# IO4-IR-Detector-Active-Fingers.net
KiCad netlist of a schematic drawn in EAGLE
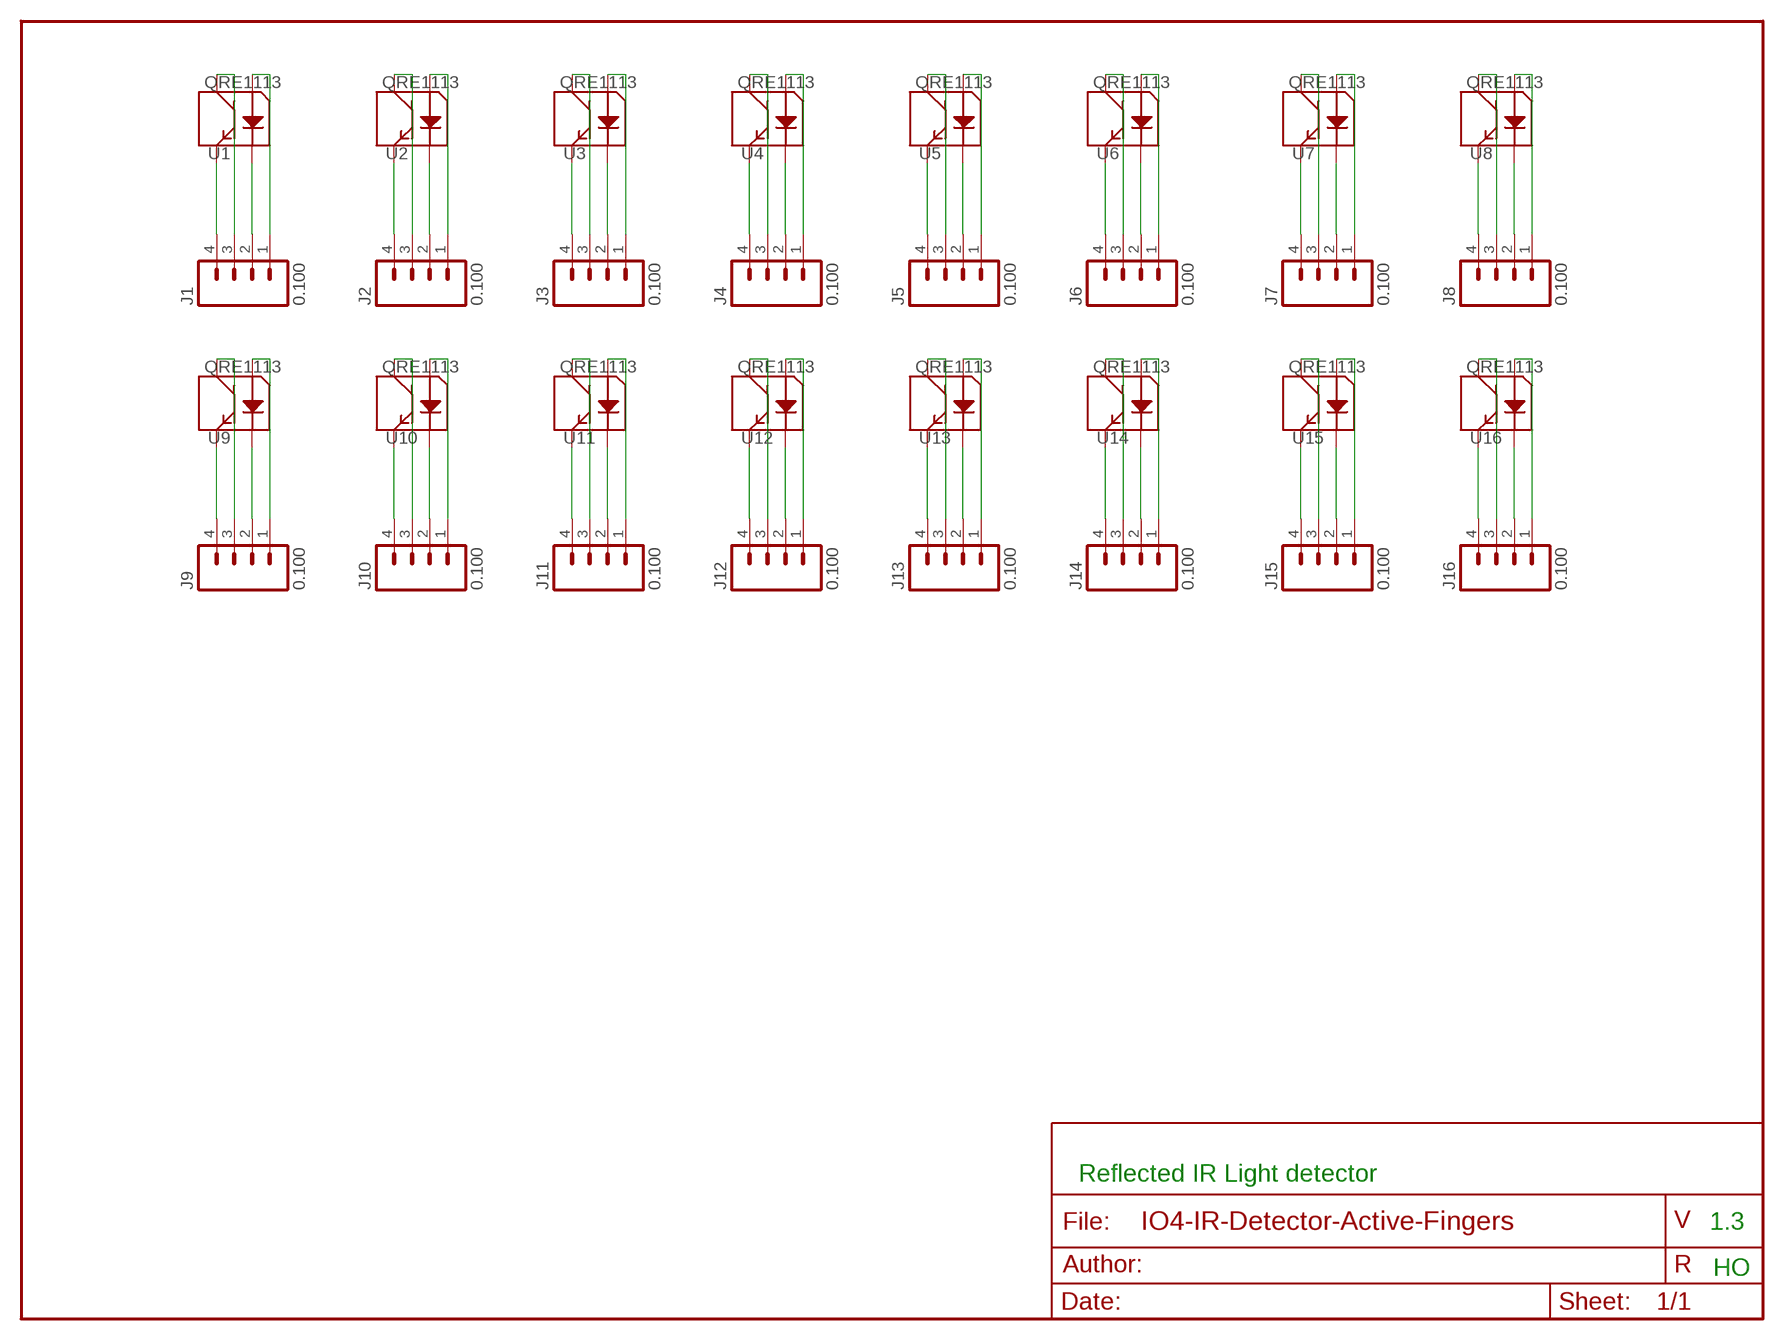
[diagram p0: schematic, sheet 1]

(export (version "E")
  (design (tool "Eeschema 10.0.6"))
  (components
    (comp (ref "J1")
      (value "0.100")
      (footprint "eagle-import:1X04_LOCK")
      (libsource (lib "eagle-import") (part "CONNECTOR-M04LOCK"))
    )
    (comp (ref "J2")
      (value "0.100")
      (footprint "eagle-import:1X04_LOCK")
      (libsource (lib "eagle-import") (part "CONNECTOR-M04LOCK"))
    )
    (comp (ref "J3")
      (value "0.100")
      (footprint "eagle-import:1X04_LOCK")
      (libsource (lib "eagle-import") (part "CONNECTOR-M04LOCK"))
    )
    (comp (ref "J4")
      (value "0.100")
      (footprint "eagle-import:1X04_LOCK")
      (libsource (lib "eagle-import") (part "CONNECTOR-M04LOCK"))
    )
    (comp (ref "J5")
      (value "0.100")
      (footprint "eagle-import:1X04_LOCK")
      (libsource (lib "eagle-import") (part "CONNECTOR-M04LOCK"))
    )
    (comp (ref "J6")
      (value "0.100")
      (footprint "eagle-import:1X04_LOCK")
      (libsource (lib "eagle-import") (part "CONNECTOR-M04LOCK"))
    )
    (comp (ref "J7")
      (value "0.100")
      (footprint "eagle-import:1X04_LOCK")
      (libsource (lib "eagle-import") (part "CONNECTOR-M04LOCK"))
    )
    (comp (ref "J8")
      (value "0.100")
      (footprint "eagle-import:1X04_LOCK")
      (libsource (lib "eagle-import") (part "CONNECTOR-M04LOCK"))
    )
    (comp (ref "J9")
      (value "0.100")
      (footprint "eagle-import:1X04_LOCK")
      (libsource (lib "eagle-import") (part "CONNECTOR-M04LOCK"))
    )
    (comp (ref "J10")
      (value "0.100")
      (footprint "eagle-import:1X04_LOCK")
      (libsource (lib "eagle-import") (part "CONNECTOR-M04LOCK"))
    )
    (comp (ref "J11")
      (value "0.100")
      (footprint "eagle-import:1X04_LOCK")
      (libsource (lib "eagle-import") (part "CONNECTOR-M04LOCK"))
    )
    (comp (ref "J12")
      (value "0.100")
      (footprint "eagle-import:1X04_LOCK")
      (libsource (lib "eagle-import") (part "CONNECTOR-M04LOCK"))
    )
    (comp (ref "J13")
      (value "0.100")
      (footprint "eagle-import:1X04_LOCK")
      (libsource (lib "eagle-import") (part "CONNECTOR-M04LOCK"))
    )
    (comp (ref "J14")
      (value "0.100")
      (footprint "eagle-import:1X04_LOCK")
      (libsource (lib "eagle-import") (part "CONNECTOR-M04LOCK"))
    )
    (comp (ref "J15")
      (value "0.100")
      (footprint "eagle-import:1X04_LOCK")
      (libsource (lib "eagle-import") (part "CONNECTOR-M04LOCK"))
    )
    (comp (ref "J16")
      (value "0.100")
      (footprint "eagle-import:1X04_LOCK")
      (libsource (lib "eagle-import") (part "CONNECTOR-M04LOCK"))
    )
    (comp (ref "U1")
      (value "QRE1113")
      (footprint "eagle-import:QRE1113")
      (libsource (lib "eagle-import") (part "QRE1113"))
    )
    (comp (ref "U2")
      (value "QRE1113")
      (footprint "eagle-import:QRE1113")
      (libsource (lib "eagle-import") (part "QRE1113"))
    )
    (comp (ref "U3")
      (value "QRE1113")
      (footprint "eagle-import:QRE1113")
      (libsource (lib "eagle-import") (part "QRE1113"))
    )
    (comp (ref "U4")
      (value "QRE1113")
      (footprint "eagle-import:QRE1113")
      (libsource (lib "eagle-import") (part "QRE1113"))
    )
    (comp (ref "U5")
      (value "QRE1113")
      (footprint "eagle-import:QRE1113")
      (libsource (lib "eagle-import") (part "QRE1113"))
    )
    (comp (ref "U6")
      (value "QRE1113")
      (footprint "eagle-import:QRE1113")
      (libsource (lib "eagle-import") (part "QRE1113"))
    )
    (comp (ref "U7")
      (value "QRE1113")
      (footprint "eagle-import:QRE1113")
      (libsource (lib "eagle-import") (part "QRE1113"))
    )
    (comp (ref "U8")
      (value "QRE1113")
      (footprint "eagle-import:QRE1113")
      (libsource (lib "eagle-import") (part "QRE1113"))
    )
    (comp (ref "U9")
      (value "QRE1113")
      (footprint "eagle-import:QRE1113")
      (libsource (lib "eagle-import") (part "QRE1113"))
    )
    (comp (ref "U10")
      (value "QRE1113")
      (footprint "eagle-import:QRE1113")
      (libsource (lib "eagle-import") (part "QRE1113"))
    )
    (comp (ref "U11")
      (value "QRE1113")
      (footprint "eagle-import:QRE1113")
      (libsource (lib "eagle-import") (part "QRE1113"))
    )
    (comp (ref "U12")
      (value "QRE1113")
      (footprint "eagle-import:QRE1113")
      (libsource (lib "eagle-import") (part "QRE1113"))
    )
    (comp (ref "U13")
      (value "QRE1113")
      (footprint "eagle-import:QRE1113")
      (libsource (lib "eagle-import") (part "QRE1113"))
    )
    (comp (ref "U14")
      (value "QRE1113")
      (footprint "eagle-import:QRE1113")
      (libsource (lib "eagle-import") (part "QRE1113"))
    )
    (comp (ref "U15")
      (value "QRE1113")
      (footprint "eagle-import:QRE1113")
      (libsource (lib "eagle-import") (part "QRE1113"))
    )
    (comp (ref "U16")
      (value "QRE1113")
      (footprint "eagle-import:QRE1113")
      (libsource (lib "eagle-import") (part "QRE1113"))
    )
  )
  (nets
    (net (code "1") (name "Net-(U1-A)") (class "Default")
      (node (ref "J1") (pin "1") (pinfunction "1_1") (pintype "passive"))
      (node (ref "U1") (pin "1") (pinfunction "A_1") (pintype "bidirectional"))
    )
    (net (code "2") (name "Net-(U1-C)") (class "Default")
      (node (ref "J1") (pin "3") (pinfunction "3_3") (pintype "passive"))
      (node (ref "U1") (pin "3") (pinfunction "C_3") (pintype "bidirectional"))
    )
    (net (code "3") (name "Net-(U1-E)") (class "Default")
      (node (ref "J1") (pin "4") (pinfunction "4_4") (pintype "passive"))
      (node (ref "U1") (pin "4") (pinfunction "E_4") (pintype "bidirectional"))
    )
    (net (code "4") (name "Net-(U1-K)") (class "Default")
      (node (ref "J1") (pin "2") (pinfunction "2_2") (pintype "passive"))
      (node (ref "U1") (pin "2") (pinfunction "K_2") (pintype "bidirectional"))
    )
    (net (code "5") (name "Net-(U2-A)") (class "Default")
      (node (ref "J2") (pin "1") (pinfunction "1_1") (pintype "passive"))
      (node (ref "U2") (pin "1") (pinfunction "A_1") (pintype "bidirectional"))
    )
    (net (code "6") (name "Net-(U2-C)") (class "Default")
      (node (ref "J2") (pin "3") (pinfunction "3_3") (pintype "passive"))
      (node (ref "U2") (pin "3") (pinfunction "C_3") (pintype "bidirectional"))
    )
    (net (code "7") (name "Net-(U2-E)") (class "Default")
      (node (ref "J2") (pin "4") (pinfunction "4_4") (pintype "passive"))
      (node (ref "U2") (pin "4") (pinfunction "E_4") (pintype "bidirectional"))
    )
    (net (code "8") (name "Net-(U2-K)") (class "Default")
      (node (ref "J2") (pin "2") (pinfunction "2_2") (pintype "passive"))
      (node (ref "U2") (pin "2") (pinfunction "K_2") (pintype "bidirectional"))
    )
    (net (code "9") (name "Net-(U3-A)") (class "Default")
      (node (ref "J3") (pin "1") (pinfunction "1_1") (pintype "passive"))
      (node (ref "U3") (pin "1") (pinfunction "A_1") (pintype "bidirectional"))
    )
    (net (code "10") (name "Net-(U3-C)") (class "Default")
      (node (ref "J3") (pin "3") (pinfunction "3_3") (pintype "passive"))
      (node (ref "U3") (pin "3") (pinfunction "C_3") (pintype "bidirectional"))
    )
    (net (code "11") (name "Net-(U3-E)") (class "Default")
      (node (ref "J3") (pin "4") (pinfunction "4_4") (pintype "passive"))
      (node (ref "U3") (pin "4") (pinfunction "E_4") (pintype "bidirectional"))
    )
    (net (code "12") (name "Net-(U3-K)") (class "Default")
      (node (ref "J3") (pin "2") (pinfunction "2_2") (pintype "passive"))
      (node (ref "U3") (pin "2") (pinfunction "K_2") (pintype "bidirectional"))
    )
    (net (code "13") (name "Net-(U4-A)") (class "Default")
      (node (ref "J4") (pin "1") (pinfunction "1_1") (pintype "passive"))
      (node (ref "U4") (pin "1") (pinfunction "A_1") (pintype "bidirectional"))
    )
    (net (code "14") (name "Net-(U4-C)") (class "Default")
      (node (ref "J4") (pin "3") (pinfunction "3_3") (pintype "passive"))
      (node (ref "U4") (pin "3") (pinfunction "C_3") (pintype "bidirectional"))
    )
    (net (code "15") (name "Net-(U4-E)") (class "Default")
      (node (ref "J4") (pin "4") (pinfunction "4_4") (pintype "passive"))
      (node (ref "U4") (pin "4") (pinfunction "E_4") (pintype "bidirectional"))
    )
    (net (code "16") (name "Net-(U4-K)") (class "Default")
      (node (ref "J4") (pin "2") (pinfunction "2_2") (pintype "passive"))
      (node (ref "U4") (pin "2") (pinfunction "K_2") (pintype "bidirectional"))
    )
    (net (code "17") (name "Net-(U5-A)") (class "Default")
      (node (ref "J5") (pin "1") (pinfunction "1_1") (pintype "passive"))
      (node (ref "U5") (pin "1") (pinfunction "A_1") (pintype "bidirectional"))
    )
    (net (code "18") (name "Net-(U5-C)") (class "Default")
      (node (ref "J5") (pin "3") (pinfunction "3_3") (pintype "passive"))
      (node (ref "U5") (pin "3") (pinfunction "C_3") (pintype "bidirectional"))
    )
    (net (code "19") (name "Net-(U5-E)") (class "Default")
      (node (ref "J5") (pin "4") (pinfunction "4_4") (pintype "passive"))
      (node (ref "U5") (pin "4") (pinfunction "E_4") (pintype "bidirectional"))
    )
    (net (code "20") (name "Net-(U5-K)") (class "Default")
      (node (ref "J5") (pin "2") (pinfunction "2_2") (pintype "passive"))
      (node (ref "U5") (pin "2") (pinfunction "K_2") (pintype "bidirectional"))
    )
    (net (code "21") (name "Net-(U6-A)") (class "Default")
      (node (ref "J6") (pin "1") (pinfunction "1_1") (pintype "passive"))
      (node (ref "U6") (pin "1") (pinfunction "A_1") (pintype "bidirectional"))
    )
    (net (code "22") (name "Net-(U6-C)") (class "Default")
      (node (ref "J6") (pin "3") (pinfunction "3_3") (pintype "passive"))
      (node (ref "U6") (pin "3") (pinfunction "C_3") (pintype "bidirectional"))
    )
    (net (code "23") (name "Net-(U6-E)") (class "Default")
      (node (ref "J6") (pin "4") (pinfunction "4_4") (pintype "passive"))
      (node (ref "U6") (pin "4") (pinfunction "E_4") (pintype "bidirectional"))
    )
    (net (code "24") (name "Net-(U6-K)") (class "Default")
      (node (ref "J6") (pin "2") (pinfunction "2_2") (pintype "passive"))
      (node (ref "U6") (pin "2") (pinfunction "K_2") (pintype "bidirectional"))
    )
    (net (code "25") (name "Net-(U7-A)") (class "Default")
      (node (ref "J7") (pin "1") (pinfunction "1_1") (pintype "passive"))
      (node (ref "U7") (pin "1") (pinfunction "A_1") (pintype "bidirectional"))
    )
    (net (code "26") (name "Net-(U7-C)") (class "Default")
      (node (ref "J7") (pin "3") (pinfunction "3_3") (pintype "passive"))
      (node (ref "U7") (pin "3") (pinfunction "C_3") (pintype "bidirectional"))
    )
    (net (code "27") (name "Net-(U7-E)") (class "Default")
      (node (ref "J7") (pin "4") (pinfunction "4_4") (pintype "passive"))
      (node (ref "U7") (pin "4") (pinfunction "E_4") (pintype "bidirectional"))
    )
    (net (code "28") (name "Net-(U7-K)") (class "Default")
      (node (ref "J7") (pin "2") (pinfunction "2_2") (pintype "passive"))
      (node (ref "U7") (pin "2") (pinfunction "K_2") (pintype "bidirectional"))
    )
    (net (code "29") (name "Net-(U8-A)") (class "Default")
      (node (ref "J8") (pin "1") (pinfunction "1_1") (pintype "passive"))
      (node (ref "U8") (pin "1") (pinfunction "A_1") (pintype "bidirectional"))
    )
    (net (code "30") (name "Net-(U8-C)") (class "Default")
      (node (ref "J8") (pin "3") (pinfunction "3_3") (pintype "passive"))
      (node (ref "U8") (pin "3") (pinfunction "C_3") (pintype "bidirectional"))
    )
    (net (code "31") (name "Net-(U8-E)") (class "Default")
      (node (ref "J8") (pin "4") (pinfunction "4_4") (pintype "passive"))
      (node (ref "U8") (pin "4") (pinfunction "E_4") (pintype "bidirectional"))
    )
    (net (code "32") (name "Net-(U8-K)") (class "Default")
      (node (ref "J8") (pin "2") (pinfunction "2_2") (pintype "passive"))
      (node (ref "U8") (pin "2") (pinfunction "K_2") (pintype "bidirectional"))
    )
    (net (code "33") (name "Net-(U9-A)") (class "Default")
      (node (ref "J9") (pin "1") (pinfunction "1_1") (pintype "passive"))
      (node (ref "U9") (pin "1") (pinfunction "A_1") (pintype "bidirectional"))
    )
    (net (code "34") (name "Net-(U9-C)") (class "Default")
      (node (ref "J9") (pin "3") (pinfunction "3_3") (pintype "passive"))
      (node (ref "U9") (pin "3") (pinfunction "C_3") (pintype "bidirectional"))
    )
    (net (code "35") (name "Net-(U9-E)") (class "Default")
      (node (ref "J9") (pin "4") (pinfunction "4_4") (pintype "passive"))
      (node (ref "U9") (pin "4") (pinfunction "E_4") (pintype "bidirectional"))
    )
    (net (code "36") (name "Net-(U9-K)") (class "Default")
      (node (ref "J9") (pin "2") (pinfunction "2_2") (pintype "passive"))
      (node (ref "U9") (pin "2") (pinfunction "K_2") (pintype "bidirectional"))
    )
    (net (code "37") (name "Net-(U10-A)") (class "Default")
      (node (ref "J10") (pin "1") (pinfunction "1_1") (pintype "passive"))
      (node (ref "U10") (pin "1") (pinfunction "A_1") (pintype "bidirectional"))
    )
    (net (code "38") (name "Net-(U10-C)") (class "Default")
      (node (ref "J10") (pin "3") (pinfunction "3_3") (pintype "passive"))
      (node (ref "U10") (pin "3") (pinfunction "C_3") (pintype "bidirectional"))
    )
    (net (code "39") (name "Net-(U10-E)") (class "Default")
      (node (ref "J10") (pin "4") (pinfunction "4_4") (pintype "passive"))
      (node (ref "U10") (pin "4") (pinfunction "E_4") (pintype "bidirectional"))
    )
    (net (code "40") (name "Net-(U10-K)") (class "Default")
      (node (ref "J10") (pin "2") (pinfunction "2_2") (pintype "passive"))
      (node (ref "U10") (pin "2") (pinfunction "K_2") (pintype "bidirectional"))
    )
    (net (code "41") (name "Net-(U11-A)") (class "Default")
      (node (ref "J11") (pin "1") (pinfunction "1_1") (pintype "passive"))
      (node (ref "U11") (pin "1") (pinfunction "A_1") (pintype "bidirectional"))
    )
    (net (code "42") (name "Net-(U11-C)") (class "Default")
      (node (ref "J11") (pin "3") (pinfunction "3_3") (pintype "passive"))
      (node (ref "U11") (pin "3") (pinfunction "C_3") (pintype "bidirectional"))
    )
    (net (code "43") (name "Net-(U11-E)") (class "Default")
      (node (ref "J11") (pin "4") (pinfunction "4_4") (pintype "passive"))
      (node (ref "U11") (pin "4") (pinfunction "E_4") (pintype "bidirectional"))
    )
    (net (code "44") (name "Net-(U11-K)") (class "Default")
      (node (ref "J11") (pin "2") (pinfunction "2_2") (pintype "passive"))
      (node (ref "U11") (pin "2") (pinfunction "K_2") (pintype "bidirectional"))
    )
    (net (code "45") (name "Net-(U12-A)") (class "Default")
      (node (ref "J12") (pin "1") (pinfunction "1_1") (pintype "passive"))
      (node (ref "U12") (pin "1") (pinfunction "A_1") (pintype "bidirectional"))
    )
    (net (code "46") (name "Net-(U12-C)") (class "Default")
      (node (ref "J12") (pin "3") (pinfunction "3_3") (pintype "passive"))
      (node (ref "U12") (pin "3") (pinfunction "C_3") (pintype "bidirectional"))
    )
    (net (code "47") (name "Net-(U12-E)") (class "Default")
      (node (ref "J12") (pin "4") (pinfunction "4_4") (pintype "passive"))
      (node (ref "U12") (pin "4") (pinfunction "E_4") (pintype "bidirectional"))
    )
    (net (code "48") (name "Net-(U12-K)") (class "Default")
      (node (ref "J12") (pin "2") (pinfunction "2_2") (pintype "passive"))
      (node (ref "U12") (pin "2") (pinfunction "K_2") (pintype "bidirectional"))
    )
    (net (code "49") (name "Net-(U13-A)") (class "Default")
      (node (ref "J13") (pin "1") (pinfunction "1_1") (pintype "passive"))
      (node (ref "U13") (pin "1") (pinfunction "A_1") (pintype "bidirectional"))
    )
    (net (code "50") (name "Net-(U13-C)") (class "Default")
      (node (ref "J13") (pin "3") (pinfunction "3_3") (pintype "passive"))
      (node (ref "U13") (pin "3") (pinfunction "C_3") (pintype "bidirectional"))
    )
    (net (code "51") (name "Net-(U13-E)") (class "Default")
      (node (ref "J13") (pin "4") (pinfunction "4_4") (pintype "passive"))
      (node (ref "U13") (pin "4") (pinfunction "E_4") (pintype "bidirectional"))
    )
    (net (code "52") (name "Net-(U13-K)") (class "Default")
      (node (ref "J13") (pin "2") (pinfunction "2_2") (pintype "passive"))
      (node (ref "U13") (pin "2") (pinfunction "K_2") (pintype "bidirectional"))
    )
    (net (code "53") (name "Net-(U14-A)") (class "Default")
      (node (ref "J14") (pin "1") (pinfunction "1_1") (pintype "passive"))
      (node (ref "U14") (pin "1") (pinfunction "A_1") (pintype "bidirectional"))
    )
    (net (code "54") (name "Net-(U14-C)") (class "Default")
      (node (ref "J14") (pin "3") (pinfunction "3_3") (pintype "passive"))
      (node (ref "U14") (pin "3") (pinfunction "C_3") (pintype "bidirectional"))
    )
    (net (code "55") (name "Net-(U14-E)") (class "Default")
      (node (ref "J14") (pin "4") (pinfunction "4_4") (pintype "passive"))
      (node (ref "U14") (pin "4") (pinfunction "E_4") (pintype "bidirectional"))
    )
    (net (code "56") (name "Net-(U14-K)") (class "Default")
      (node (ref "J14") (pin "2") (pinfunction "2_2") (pintype "passive"))
      (node (ref "U14") (pin "2") (pinfunction "K_2") (pintype "bidirectional"))
    )
    (net (code "57") (name "Net-(U15-A)") (class "Default")
      (node (ref "J15") (pin "1") (pinfunction "1_1") (pintype "passive"))
      (node (ref "U15") (pin "1") (pinfunction "A_1") (pintype "bidirectional"))
    )
    (net (code "58") (name "Net-(U15-C)") (class "Default")
      (node (ref "J15") (pin "3") (pinfunction "3_3") (pintype "passive"))
      (node (ref "U15") (pin "3") (pinfunction "C_3") (pintype "bidirectional"))
    )
    (net (code "59") (name "Net-(U15-E)") (class "Default")
      (node (ref "J15") (pin "4") (pinfunction "4_4") (pintype "passive"))
      (node (ref "U15") (pin "4") (pinfunction "E_4") (pintype "bidirectional"))
    )
    (net (code "60") (name "Net-(U15-K)") (class "Default")
      (node (ref "J15") (pin "2") (pinfunction "2_2") (pintype "passive"))
      (node (ref "U15") (pin "2") (pinfunction "K_2") (pintype "bidirectional"))
    )
    (net (code "61") (name "Net-(U16-A)") (class "Default")
      (node (ref "J16") (pin "1") (pinfunction "1_1") (pintype "passive"))
      (node (ref "U16") (pin "1") (pinfunction "A_1") (pintype "bidirectional"))
    )
    (net (code "62") (name "Net-(U16-C)") (class "Default")
      (node (ref "J16") (pin "3") (pinfunction "3_3") (pintype "passive"))
      (node (ref "U16") (pin "3") (pinfunction "C_3") (pintype "bidirectional"))
    )
    (net (code "63") (name "Net-(U16-E)") (class "Default")
      (node (ref "J16") (pin "4") (pinfunction "4_4") (pintype "passive"))
      (node (ref "U16") (pin "4") (pinfunction "E_4") (pintype "bidirectional"))
    )
    (net (code "64") (name "Net-(U16-K)") (class "Default")
      (node (ref "J16") (pin "2") (pinfunction "2_2") (pintype "passive"))
      (node (ref "U16") (pin "2") (pinfunction "K_2") (pintype "bidirectional"))
    )
  )
)
